# fpga-bank0.net
KiCad netlist of a schematic drawn in Altium Designer
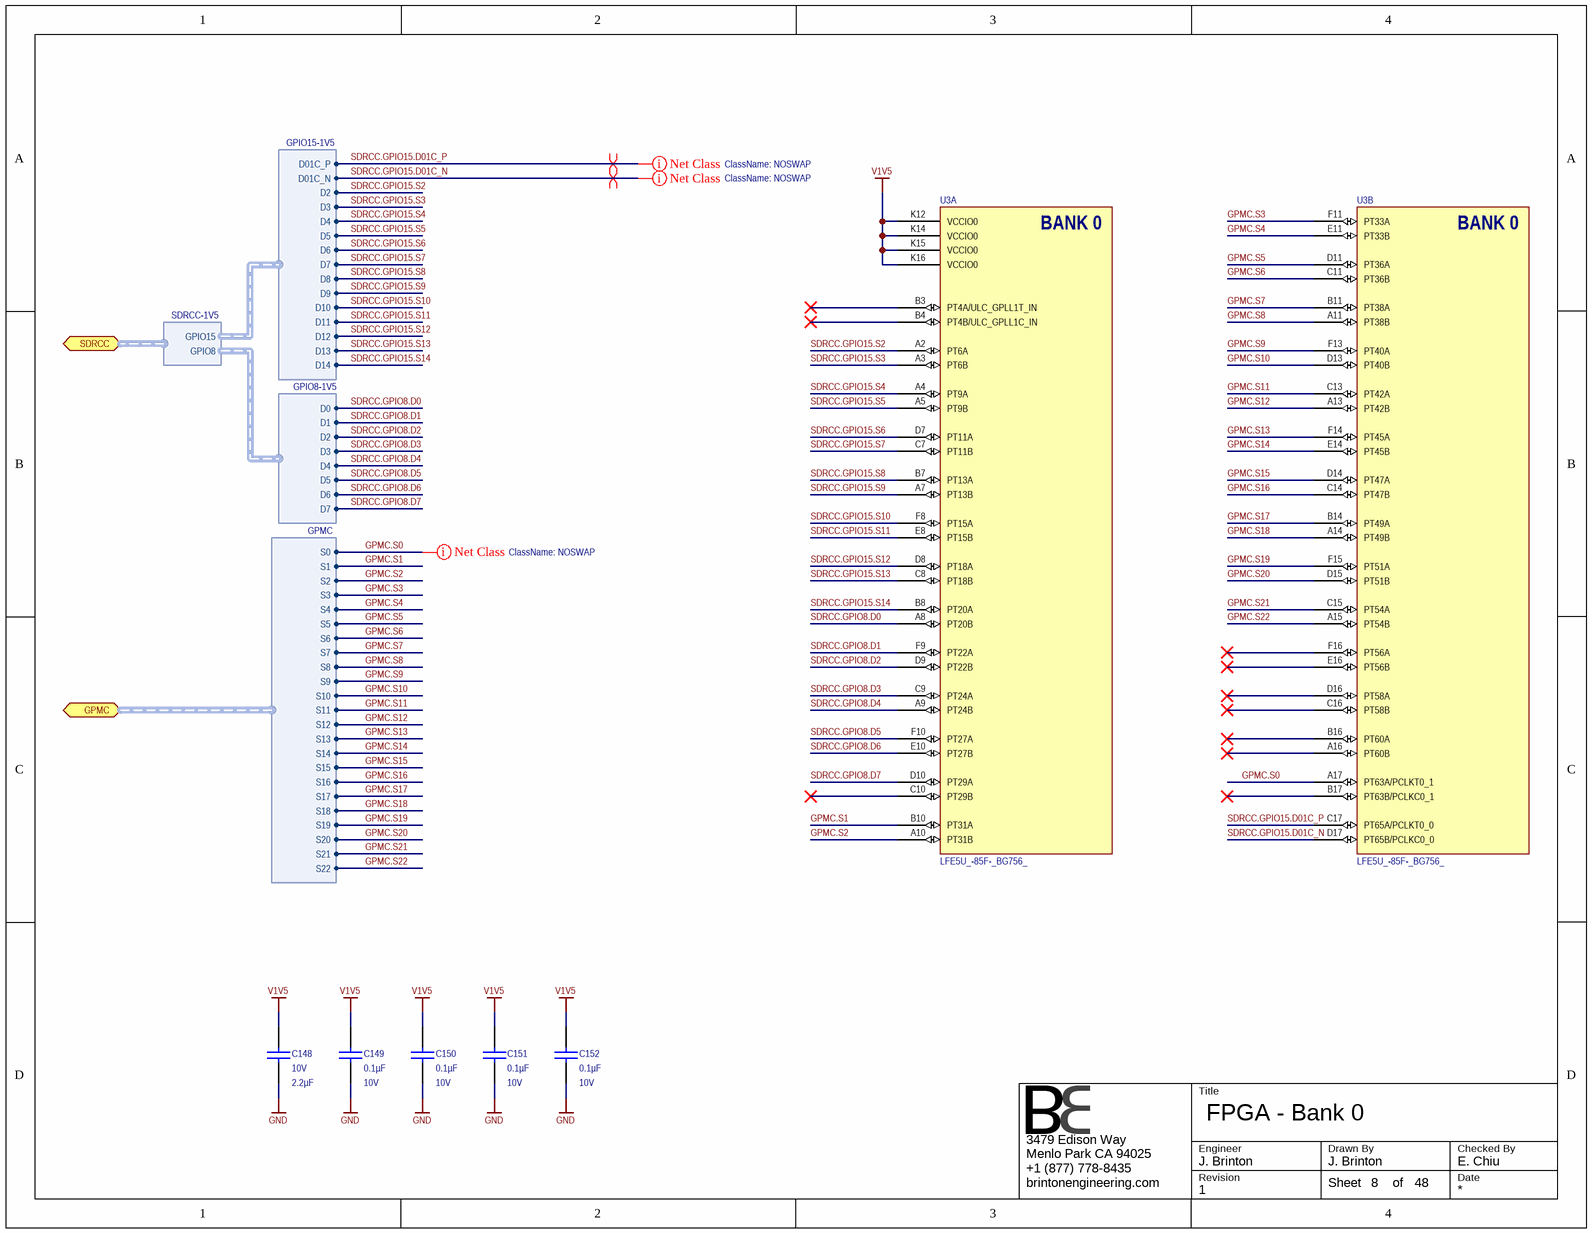
[diagram p0: fpga-bank0.SchDoc]

(export (version "E")
  (design (tool "Eeschema 10.0.6"))
  (components
    (comp (ref "C148")
      (value "GRM188R71A225KE15D")
      (footprint "CAPC1608X90N")
      (description "CAP CER 2.2UF 10V 10% X7R 0603")
      (fields
        (field (name "MANUFACTURER") "Murata Electronics North America")
        (field (name "TOLERANCE") "±10%")
        (field (name "VOLTAGE - RATED") "10V")
        (field (name "CAPACITANCE") "2.2µF")
      )
      (libsource (lib "murata") (part "GRM188R71A225KE15D"))
    )
    (comp (ref "C149")
      (value "GRM155R71A104KA01J")
      (footprint "CAPC1005X56N")
      (description "CAP CER 0.1UF 10V 10% X7R 0402")
      (fields
        (field (name "MANUFACTURER") "Murata Electronics North America")
        (field (name "TOLERANCE") "±10%")
        (field (name "CAPACITANCE") "0.1µF")
        (field (name "VOLTAGE - RATED") "10V")
      )
      (libsource (lib "murata") (part "GRM155R71A104KA01J"))
    )
    (comp (ref "C150")
      (value "GRM155R71A104KA01J")
      (footprint "CAPC1005X56N")
      (description "CAP CER 0.1UF 10V 10% X7R 0402")
      (fields
        (field (name "MANUFACTURER") "Murata Electronics North America")
        (field (name "TOLERANCE") "±10%")
        (field (name "CAPACITANCE") "0.1µF")
        (field (name "VOLTAGE - RATED") "10V")
      )
      (libsource (lib "murata") (part "GRM155R71A104KA01J"))
    )
    (comp (ref "C151")
      (value "GRM155R71A104KA01J")
      (footprint "CAPC1005X56N")
      (description "CAP CER 0.1UF 10V 10% X7R 0402")
      (fields
        (field (name "MANUFACTURER") "Murata Electronics North America")
        (field (name "TOLERANCE") "±10%")
        (field (name "CAPACITANCE") "0.1µF")
        (field (name "VOLTAGE - RATED") "10V")
      )
      (libsource (lib "murata") (part "GRM155R71A104KA01J"))
    )
    (comp (ref "C152")
      (value "GRM155R71A104KA01J")
      (footprint "CAPC1005X56N")
      (description "CAP CER 0.1UF 10V 10% X7R 0402")
      (fields
        (field (name "MANUFACTURER") "Murata Electronics North America")
        (field (name "TOLERANCE") "±10%")
        (field (name "CAPACITANCE") "0.1µF")
        (field (name "VOLTAGE - RATED") "10V")
      )
      (libsource (lib "murata") (part "GRM155R71A104KA01J"))
    )
    (comp (ref "U3")
      (value "LFE5U_-85F-_BG756_")
      (footprint "lattice:caBGA756")
      (description "ECP5 FPGA, 85k LUT, 756-caBGA")
      (fields (field (name "MANUFACTURER") "Lattice Semiconductor"))
      (libsource (lib "lattice") (part "LFE5U_-85F-_BG756_"))
    )
  )
  (nets
    (net (code "4") (name "/GPMC.S0") (class "Default")
      (node (ref "U3") (pin "A17") (pinfunction "PT63A/PCLKT0_1_A17") (pintype "bidirectional"))
    )
    (net (code "5") (name "/GPMC.S1") (class "Default")
      (node (ref "U3") (pin "B10") (pinfunction "PT31A_B10") (pintype "bidirectional"))
    )
    (net (code "6") (name "/GPMC.S2") (class "Default")
      (node (ref "U3") (pin "A10") (pinfunction "PT31B_A10") (pintype "bidirectional"))
    )
    (net (code "7") (name "/GPMC.S3") (class "Default")
      (node (ref "U3") (pin "F11") (pinfunction "PT33A_F11") (pintype "bidirectional"))
    )
    (net (code "8") (name "/GPMC.S4") (class "Default")
      (node (ref "U3") (pin "E11") (pinfunction "PT33B_E11") (pintype "bidirectional"))
    )
    (net (code "9") (name "/GPMC.S5") (class "Default")
      (node (ref "U3") (pin "D11") (pinfunction "PT36A_D11") (pintype "bidirectional"))
    )
    (net (code "10") (name "/GPMC.S6") (class "Default")
      (node (ref "U3") (pin "C11") (pinfunction "PT36B_C11") (pintype "bidirectional"))
    )
    (net (code "11") (name "/GPMC.S7") (class "Default")
      (node (ref "U3") (pin "B11") (pinfunction "PT38A_B11") (pintype "bidirectional"))
    )
    (net (code "12") (name "/GPMC.S8") (class "Default")
      (node (ref "U3") (pin "A11") (pinfunction "PT38B_A11") (pintype "bidirectional"))
    )
    (net (code "13") (name "/GPMC.S9") (class "Default")
      (node (ref "U3") (pin "F13") (pinfunction "PT40A_F13") (pintype "bidirectional"))
    )
    (net (code "14") (name "/GPMC.S10") (class "Default")
      (node (ref "U3") (pin "D13") (pinfunction "PT40B_D13") (pintype "bidirectional"))
    )
    (net (code "15") (name "/GPMC.S11") (class "Default")
      (node (ref "U3") (pin "C13") (pinfunction "PT42A_C13") (pintype "bidirectional"))
    )
    (net (code "16") (name "/GPMC.S12") (class "Default")
      (node (ref "U3") (pin "A13") (pinfunction "PT42B_A13") (pintype "bidirectional"))
    )
    (net (code "17") (name "/GPMC.S13") (class "Default")
      (node (ref "U3") (pin "F14") (pinfunction "PT45A_F14") (pintype "bidirectional"))
    )
    (net (code "18") (name "/GPMC.S14") (class "Default")
      (node (ref "U3") (pin "E14") (pinfunction "PT45B_E14") (pintype "bidirectional"))
    )
    (net (code "19") (name "/GPMC.S15") (class "Default")
      (node (ref "U3") (pin "D14") (pinfunction "PT47A_D14") (pintype "bidirectional"))
    )
    (net (code "20") (name "/GPMC.S16") (class "Default")
      (node (ref "U3") (pin "C14") (pinfunction "PT47B_C14") (pintype "bidirectional"))
    )
    (net (code "21") (name "/GPMC.S17") (class "Default")
      (node (ref "U3") (pin "B14") (pinfunction "PT49A_B14") (pintype "bidirectional"))
    )
    (net (code "22") (name "/GPMC.S18") (class "Default")
      (node (ref "U3") (pin "A14") (pinfunction "PT49B_A14") (pintype "bidirectional"))
    )
    (net (code "23") (name "/GPMC.S19") (class "Default")
      (node (ref "U3") (pin "F15") (pinfunction "PT51A_F15") (pintype "bidirectional"))
    )
    (net (code "24") (name "/GPMC.S20") (class "Default")
      (node (ref "U3") (pin "D15") (pinfunction "PT51B_D15") (pintype "bidirectional"))
    )
    (net (code "25") (name "/GPMC.S21") (class "Default")
      (node (ref "U3") (pin "C15") (pinfunction "PT54A_C15") (pintype "bidirectional"))
    )
    (net (code "26") (name "/GPMC.S22") (class "Default")
      (node (ref "U3") (pin "A15") (pinfunction "PT54B_A15") (pintype "bidirectional"))
    )
    (net (code "27") (name "/SDRCC.GPIO8.D0") (class "Default")
      (node (ref "U3") (pin "A8") (pinfunction "PT20B_A8") (pintype "bidirectional"))
    )
    (net (code "28") (name "/SDRCC.GPIO8.D1") (class "Default")
      (node (ref "U3") (pin "F9") (pinfunction "PT22A_F9") (pintype "bidirectional"))
    )
    (net (code "29") (name "/SDRCC.GPIO8.D2") (class "Default")
      (node (ref "U3") (pin "D9") (pinfunction "PT22B_D9") (pintype "bidirectional"))
    )
    (net (code "30") (name "/SDRCC.GPIO8.D3") (class "Default")
      (node (ref "U3") (pin "C9") (pinfunction "PT24A_C9") (pintype "bidirectional"))
    )
    (net (code "31") (name "/SDRCC.GPIO8.D4") (class "Default")
      (node (ref "U3") (pin "A9") (pinfunction "PT24B_A9") (pintype "bidirectional"))
    )
    (net (code "32") (name "/SDRCC.GPIO8.D5") (class "Default")
      (node (ref "U3") (pin "F10") (pinfunction "PT27A_F10") (pintype "bidirectional"))
    )
    (net (code "33") (name "/SDRCC.GPIO8.D6") (class "Default")
      (node (ref "U3") (pin "E10") (pinfunction "PT27B_E10") (pintype "bidirectional"))
    )
    (net (code "34") (name "/SDRCC.GPIO8.D7") (class "Default")
      (node (ref "U3") (pin "D10") (pinfunction "PT29A_D10") (pintype "bidirectional"))
    )
    (net (code "35") (name "/SDRCC.GPIO15.D01C_N") (class "Default")
      (node (ref "U3") (pin "D17") (pinfunction "PT65B/PCLKC0_0_D17") (pintype "bidirectional"))
    )
    (net (code "36") (name "/SDRCC.GPIO15.D01C_P") (class "Default")
      (node (ref "U3") (pin "C17") (pinfunction "PT65A/PCLKT0_0_C17") (pintype "bidirectional"))
    )
    (net (code "37") (name "/SDRCC.GPIO15.S2") (class "Default")
      (node (ref "U3") (pin "A2") (pinfunction "PT6A_A2") (pintype "bidirectional"))
    )
    (net (code "38") (name "/SDRCC.GPIO15.S3") (class "Default")
      (node (ref "U3") (pin "A3") (pinfunction "PT6B_A3") (pintype "bidirectional"))
    )
    (net (code "39") (name "/SDRCC.GPIO15.S4") (class "Default")
      (node (ref "U3") (pin "A4") (pinfunction "PT9A_A4") (pintype "bidirectional"))
    )
    (net (code "40") (name "/SDRCC.GPIO15.S5") (class "Default")
      (node (ref "U3") (pin "A5") (pinfunction "PT9B_A5") (pintype "bidirectional"))
    )
    (net (code "41") (name "/SDRCC.GPIO15.S6") (class "Default")
      (node (ref "U3") (pin "D7") (pinfunction "PT11A_D7") (pintype "bidirectional"))
    )
    (net (code "42") (name "/SDRCC.GPIO15.S7") (class "Default")
      (node (ref "U3") (pin "C7") (pinfunction "PT11B_C7") (pintype "bidirectional"))
    )
    (net (code "43") (name "/SDRCC.GPIO15.S8") (class "Default")
      (node (ref "U3") (pin "B7") (pinfunction "PT13A_B7") (pintype "bidirectional"))
    )
    (net (code "44") (name "/SDRCC.GPIO15.S9") (class "Default")
      (node (ref "U3") (pin "A7") (pinfunction "PT13B_A7") (pintype "bidirectional"))
    )
    (net (code "45") (name "/SDRCC.GPIO15.S10") (class "Default")
      (node (ref "U3") (pin "F8") (pinfunction "PT15A_F8") (pintype "bidirectional"))
    )
    (net (code "46") (name "/SDRCC.GPIO15.S11") (class "Default")
      (node (ref "U3") (pin "E8") (pinfunction "PT15B_E8") (pintype "bidirectional"))
    )
    (net (code "47") (name "/SDRCC.GPIO15.S12") (class "Default")
      (node (ref "U3") (pin "D8") (pinfunction "PT18A_D8") (pintype "bidirectional"))
    )
    (net (code "48") (name "/SDRCC.GPIO15.S13") (class "Default")
      (node (ref "U3") (pin "C8") (pinfunction "PT18B_C8") (pintype "bidirectional"))
    )
    (net (code "49") (name "/SDRCC.GPIO15.S14") (class "Default")
      (node (ref "U3") (pin "B8") (pinfunction "PT20A_B8") (pintype "bidirectional"))
    )
    (net (code "53") (name "GND") (class "Default")
      (node (ref "C148") (pin "1") (pinfunction "1_1") (pintype "passive"))
      (node (ref "C149") (pin "1") (pinfunction "1_1") (pintype "passive"))
      (node (ref "C150") (pin "1") (pinfunction "1_1") (pintype "passive"))
      (node (ref "C151") (pin "1") (pinfunction "1_1") (pintype "passive"))
      (node (ref "C152") (pin "1") (pinfunction "1_1") (pintype "passive"))
    )
    (net (code "54") (name "V1V5") (class "Default")
      (node (ref "C148") (pin "2") (pinfunction "2_2") (pintype "passive"))
      (node (ref "C149") (pin "2") (pinfunction "2_2") (pintype "passive"))
      (node (ref "C150") (pin "2") (pinfunction "2_2") (pintype "passive"))
      (node (ref "C151") (pin "2") (pinfunction "2_2") (pintype "passive"))
      (node (ref "C152") (pin "2") (pinfunction "2_2") (pintype "passive"))
      (node (ref "U3") (pin "K12") (pinfunction "VCCIO0_K12") (pintype "power_in"))
      (node (ref "U3") (pin "K14") (pinfunction "VCCIO0_K14") (pintype "power_in"))
      (node (ref "U3") (pin "K15") (pinfunction "VCCIO0_K15") (pintype "power_in"))
      (node (ref "U3") (pin "K16") (pinfunction "VCCIO0_K16") (pintype "power_in"))
    )
    (net (code "55") (name "unconnected-(U3A-PT4A{slash}ULC_GPLL1T_IN-PadB3)") (class "Default")
      (node (ref "U3") (pin "B3") (pinfunction "PT4A/ULC_GPLL1T_IN_B3") (pintype "bidirectional+no_connect"))
    )
    (net (code "56") (name "unconnected-(U3A-PT4B{slash}ULC_GPLL1C_IN-PadB4)") (class "Default")
      (node (ref "U3") (pin "B4") (pinfunction "PT4B/ULC_GPLL1C_IN_B4") (pintype "bidirectional+no_connect"))
    )
    (net (code "57") (name "unconnected-(U3A-PT29B-PadC10)") (class "Default")
      (node (ref "U3") (pin "C10") (pinfunction "PT29B_C10") (pintype "bidirectional+no_connect"))
    )
    (net (code "58") (name "unconnected-(U3B-PT56A-PadF16)") (class "Default")
      (node (ref "U3") (pin "F16") (pinfunction "PT56A_F16") (pintype "bidirectional+no_connect"))
    )
    (net (code "59") (name "unconnected-(U3B-PT56B-PadE16)") (class "Default")
      (node (ref "U3") (pin "E16") (pinfunction "PT56B_E16") (pintype "bidirectional+no_connect"))
    )
    (net (code "60") (name "unconnected-(U3B-PT58A-PadD16)") (class "Default")
      (node (ref "U3") (pin "D16") (pinfunction "PT58A_D16") (pintype "bidirectional+no_connect"))
    )
    (net (code "61") (name "unconnected-(U3B-PT58B-PadC16)") (class "Default")
      (node (ref "U3") (pin "C16") (pinfunction "PT58B_C16") (pintype "bidirectional+no_connect"))
    )
    (net (code "62") (name "unconnected-(U3B-PT60A-PadB16)") (class "Default")
      (node (ref "U3") (pin "B16") (pinfunction "PT60A_B16") (pintype "bidirectional+no_connect"))
    )
    (net (code "63") (name "unconnected-(U3B-PT60B-PadA16)") (class "Default")
      (node (ref "U3") (pin "A16") (pinfunction "PT60B_A16") (pintype "bidirectional+no_connect"))
    )
    (net (code "64") (name "unconnected-(U3B-PT63B{slash}PCLKC0_1-PadB17)") (class "Default")
      (node (ref "U3") (pin "B17") (pinfunction "PT63B/PCLKC0_1_B17") (pintype "bidirectional+no_connect"))
    )
  )
)
